# 11-M2_RCB_MUX.net
KiCad netlist of a schematic drawn in Altium Designer
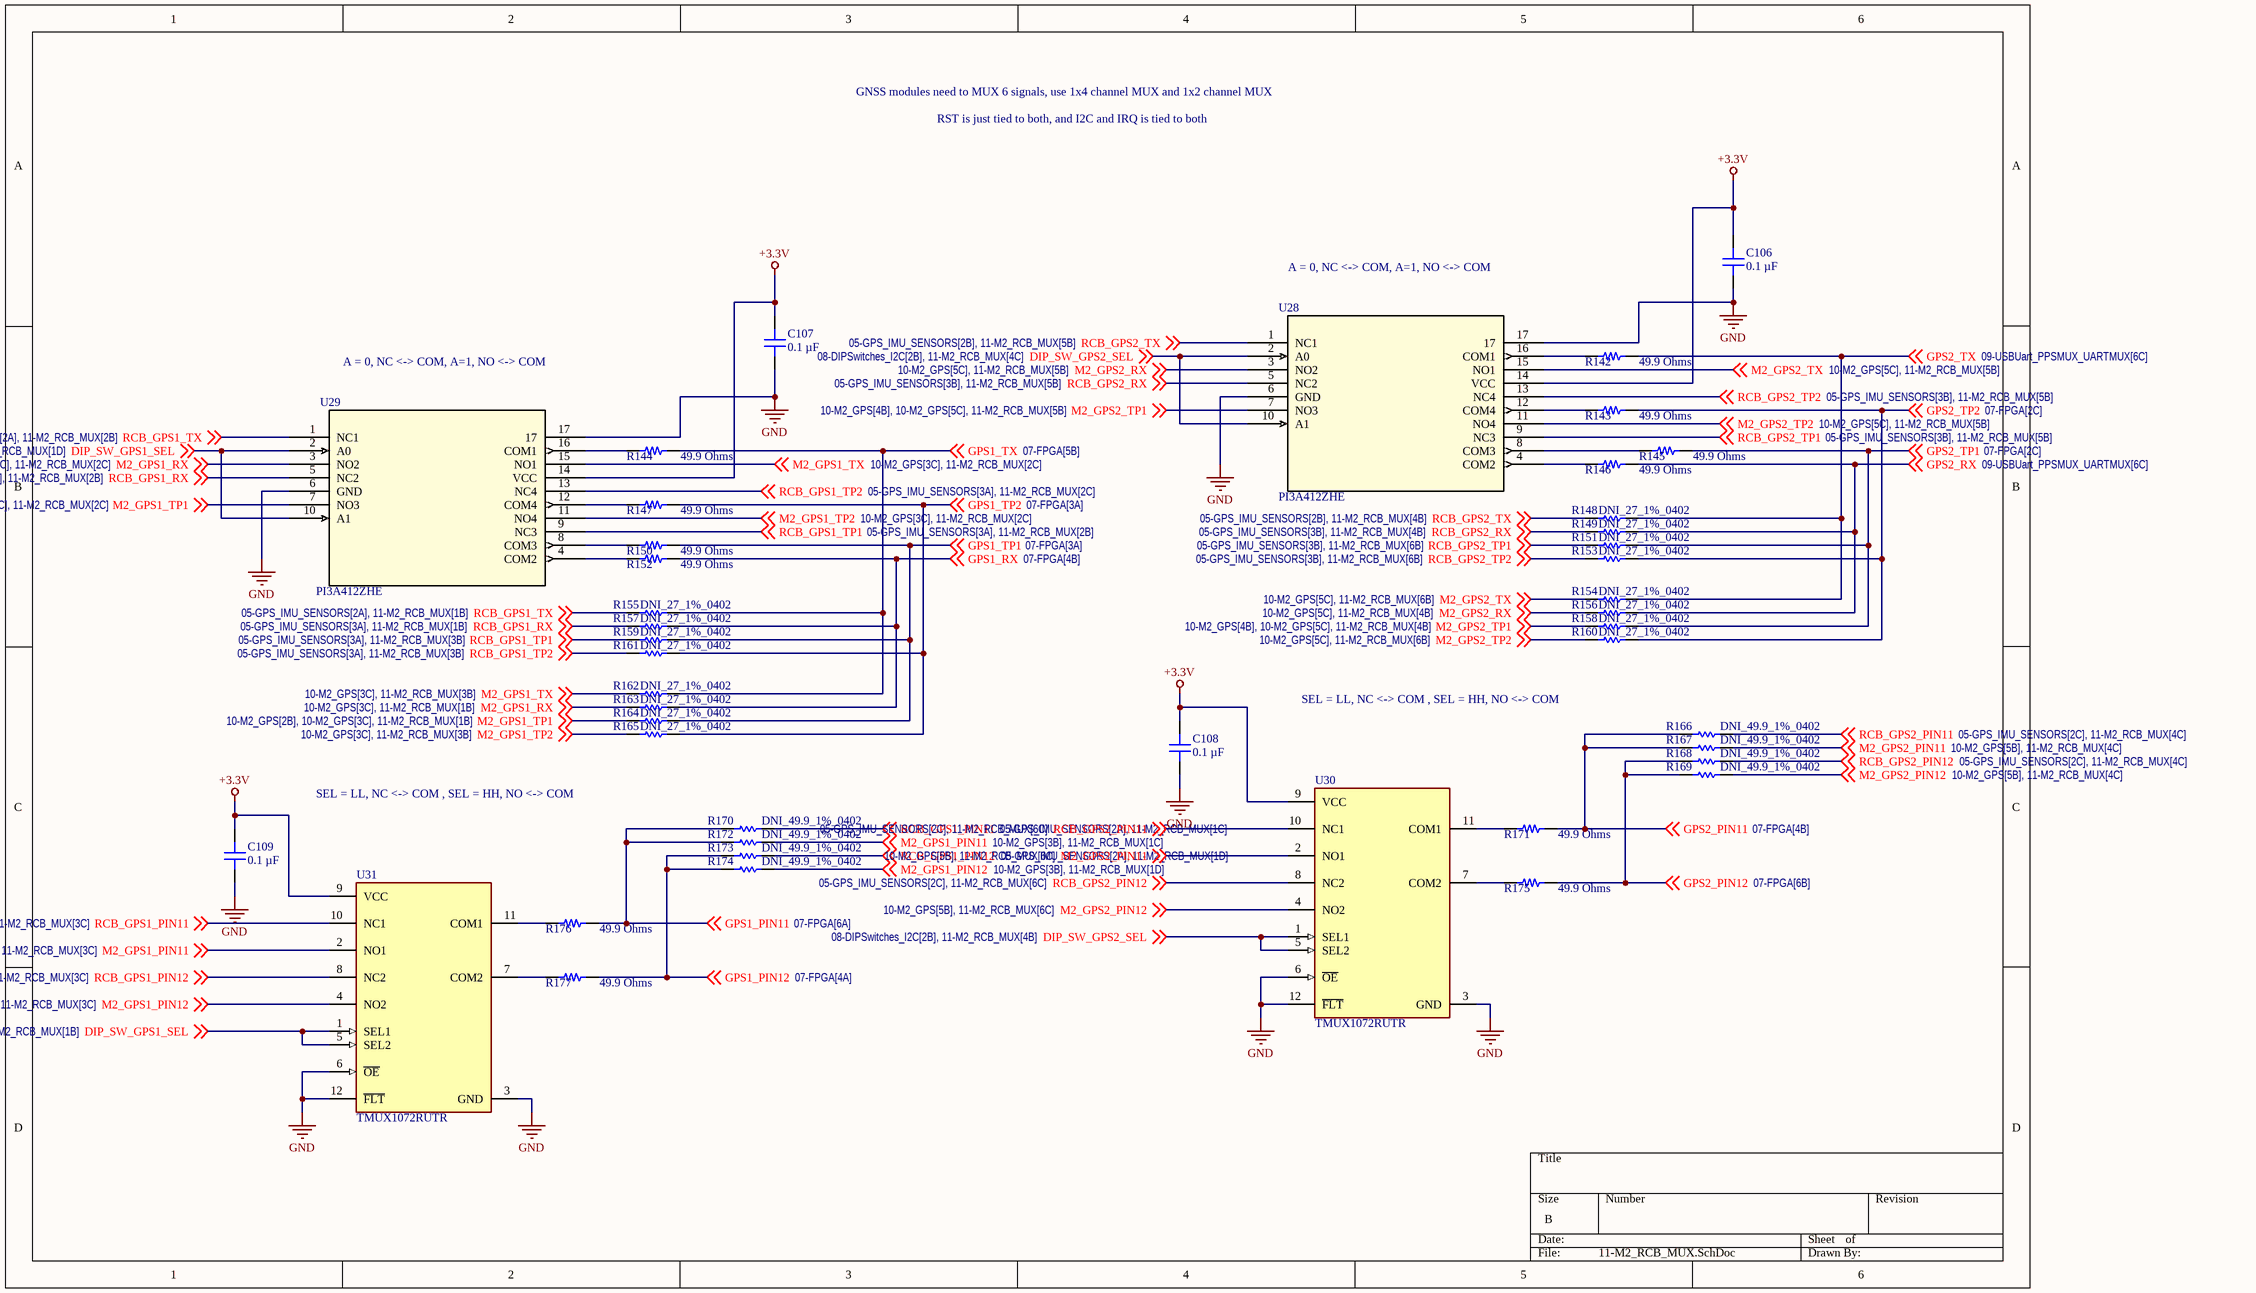
[diagram p0: 11-M2_RCB_MUX.SchDoc]

(export (version "E")
  (design (tool "Eeschema 10.0.6"))
  (components
    (comp (ref "C106")
      (value "0.1 µF")
      (footprint "CAP 0402_1005")
      (description "CAP CER 0.1UF 50V X7R 0402")
      (fields (field (name "TOLERANCE") "±10%") (field (name "PART NUMBER") "CC0402KRX7R9BB104"))
      (libsource (lib "Celestial Altium Library - altium_library") (part "Capacitor"))
    )
    (comp (ref "C107")
      (value "0.1 µF")
      (footprint "CAP 0402_1005")
      (description "CAP CER 0.1UF 50V X7R 0402")
      (fields (field (name "TOLERANCE") "±10%") (field (name "PART NUMBER") "CC0402KRX7R9BB104"))
      (libsource (lib "Celestial Altium Library - altium_library") (part "Capacitor"))
    )
    (comp (ref "C108")
      (value "0.1 µF")
      (footprint "CAP 0402_1005")
      (description "CAP CER 0.1UF 50V X7R 0402")
      (fields (field (name "TOLERANCE") "±10%") (field (name "PART NUMBER") "CC0402KRX7R9BB104"))
      (libsource (lib "Celestial Altium Library - altium_library") (part "Capacitor"))
    )
    (comp (ref "C109")
      (value "0.1 µF")
      (footprint "CAP 0402_1005")
      (description "CAP CER 0.1UF 50V X7R 0402")
      (fields (field (name "TOLERANCE") "±10%") (field (name "PART NUMBER") "CC0402KRX7R9BB104"))
      (libsource (lib "Celestial Altium Library - altium_library") (part "Capacitor"))
    )
    (comp (ref "R142")
      (value "49.9 Ohms")
      (footprint "YAGEO RES 0402_1005")
      (description "RES 49.9 OHM 1% 1/16W 0402")
      (fields (field (name "MANUFACTURER") "Yageo") (field (name "PART NUMBER") "RC0402FR-0749R9L"))
      (libsource (lib "Celestial Altium Library - altium_library") (part "Resistor"))
    )
    (comp (ref "R143")
      (value "49.9 Ohms")
      (footprint "YAGEO RES 0402_1005")
      (description "RES 49.9 OHM 1% 1/16W 0402")
      (fields (field (name "MANUFACTURER") "Yageo") (field (name "PART NUMBER") "RC0402FR-0749R9L"))
      (libsource (lib "Celestial Altium Library - altium_library") (part "Resistor"))
    )
    (comp (ref "R144")
      (value "49.9 Ohms")
      (footprint "YAGEO RES 0402_1005")
      (description "RES 49.9 OHM 1% 1/16W 0402")
      (fields (field (name "MANUFACTURER") "Yageo") (field (name "PART NUMBER") "RC0402FR-0749R9L"))
      (libsource (lib "Celestial Altium Library - altium_library") (part "Resistor"))
    )
    (comp (ref "R145")
      (value "49.9 Ohms")
      (footprint "YAGEO RES 0402_1005")
      (description "RES 49.9 OHM 1% 1/16W 0402")
      (fields (field (name "MANUFACTURER") "Yageo") (field (name "PART NUMBER") "RC0402FR-0749R9L"))
      (libsource (lib "Celestial Altium Library - altium_library") (part "Resistor"))
    )
    (comp (ref "R146")
      (value "49.9 Ohms")
      (footprint "YAGEO RES 0402_1005")
      (description "RES 49.9 OHM 1% 1/16W 0402")
      (fields (field (name "MANUFACTURER") "Yageo") (field (name "PART NUMBER") "RC0402FR-0749R9L"))
      (libsource (lib "Celestial Altium Library - altium_library") (part "Resistor"))
    )
    (comp (ref "R147")
      (value "49.9 Ohms")
      (footprint "YAGEO RES 0402_1005")
      (description "RES 49.9 OHM 1% 1/16W 0402")
      (fields (field (name "MANUFACTURER") "Yageo") (field (name "PART NUMBER") "RC0402FR-0749R9L"))
      (libsource (lib "Celestial Altium Library - altium_library") (part "Resistor"))
    )
    (comp (ref "R148")
      (value "DNI_27_1%_0402")
      (footprint "RESC1005X40X25NL05T05")
      (fields (field (name "PART NUMBER") "CRCW040227R0FKED") (field (name "MANUFACTURER") "Vishay Dale"))
      (libsource (lib "Altium Content Vault") (part "RES"))
    )
    (comp (ref "R149")
      (value "DNI_27_1%_0402")
      (footprint "RESC1005X40X25NL05T05")
      (fields (field (name "PART NUMBER") "CRCW040227R0FKED") (field (name "MANUFACTURER") "Vishay Dale"))
      (libsource (lib "Altium Content Vault") (part "RES"))
    )
    (comp (ref "R150")
      (value "49.9 Ohms")
      (footprint "YAGEO RES 0402_1005")
      (description "RES 49.9 OHM 1% 1/16W 0402")
      (fields (field (name "MANUFACTURER") "Yageo") (field (name "PART NUMBER") "RC0402FR-0749R9L"))
      (libsource (lib "Celestial Altium Library - altium_library") (part "Resistor"))
    )
    (comp (ref "R151")
      (value "DNI_27_1%_0402")
      (footprint "RESC1005X40X25NL05T05")
      (fields (field (name "PART NUMBER") "CRCW040227R0FKED") (field (name "MANUFACTURER") "Vishay Dale"))
      (libsource (lib "Altium Content Vault") (part "RES"))
    )
    (comp (ref "R152")
      (value "49.9 Ohms")
      (footprint "YAGEO RES 0402_1005")
      (description "RES 49.9 OHM 1% 1/16W 0402")
      (fields (field (name "MANUFACTURER") "Yageo") (field (name "PART NUMBER") "RC0402FR-0749R9L"))
      (libsource (lib "Celestial Altium Library - altium_library") (part "Resistor"))
    )
    (comp (ref "R153")
      (value "DNI_27_1%_0402")
      (footprint "RESC1005X40X25NL05T05")
      (fields (field (name "PART NUMBER") "CRCW040227R0FKED") (field (name "MANUFACTURER") "Vishay Dale"))
      (libsource (lib "Altium Content Vault") (part "RES"))
    )
    (comp (ref "R154")
      (value "DNI_27_1%_0402")
      (footprint "RESC1005X40X25NL05T05")
      (fields (field (name "PART NUMBER") "CRCW040227R0FKED") (field (name "MANUFACTURER") "Vishay Dale"))
      (libsource (lib "Altium Content Vault") (part "RES"))
    )
    (comp (ref "R155")
      (value "DNI_27_1%_0402")
      (footprint "RESC1005X40X25NL05T05")
      (fields (field (name "PART NUMBER") "CRCW040227R0FKED") (field (name "MANUFACTURER") "Vishay Dale"))
      (libsource (lib "Altium Content Vault") (part "RES"))
    )
    (comp (ref "R156")
      (value "DNI_27_1%_0402")
      (footprint "RESC1005X40X25NL05T05")
      (fields (field (name "PART NUMBER") "CRCW040227R0FKED") (field (name "MANUFACTURER") "Vishay Dale"))
      (libsource (lib "Altium Content Vault") (part "RES"))
    )
    (comp (ref "R157")
      (value "DNI_27_1%_0402")
      (footprint "RESC1005X40X25NL05T05")
      (fields (field (name "PART NUMBER") "CRCW040227R0FKED") (field (name "MANUFACTURER") "Vishay Dale"))
      (libsource (lib "Altium Content Vault") (part "RES"))
    )
    (comp (ref "R158")
      (value "DNI_27_1%_0402")
      (footprint "RESC1005X40X25NL05T05")
      (fields (field (name "PART NUMBER") "CRCW040227R0FKED") (field (name "MANUFACTURER") "Vishay Dale"))
      (libsource (lib "Altium Content Vault") (part "RES"))
    )
    (comp (ref "R159")
      (value "DNI_27_1%_0402")
      (footprint "RESC1005X40X25NL05T05")
      (fields (field (name "PART NUMBER") "CRCW040227R0FKED") (field (name "MANUFACTURER") "Vishay Dale"))
      (libsource (lib "Altium Content Vault") (part "RES"))
    )
    (comp (ref "R160")
      (value "DNI_27_1%_0402")
      (footprint "RESC1005X40X25NL05T05")
      (fields (field (name "PART NUMBER") "CRCW040227R0FKED") (field (name "MANUFACTURER") "Vishay Dale"))
      (libsource (lib "Altium Content Vault") (part "RES"))
    )
    (comp (ref "R161")
      (value "DNI_27_1%_0402")
      (footprint "RESC1005X40X25NL05T05")
      (fields (field (name "PART NUMBER") "CRCW040227R0FKED") (field (name "MANUFACTURER") "Vishay Dale"))
      (libsource (lib "Altium Content Vault") (part "RES"))
    )
    (comp (ref "R162")
      (value "DNI_27_1%_0402")
      (footprint "RESC1005X40X25NL05T05")
      (fields (field (name "PART NUMBER") "CRCW040227R0FKED") (field (name "MANUFACTURER") "Vishay Dale"))
      (libsource (lib "Altium Content Vault") (part "RES"))
    )
    (comp (ref "R163")
      (value "DNI_27_1%_0402")
      (footprint "RESC1005X40X25NL05T05")
      (fields (field (name "PART NUMBER") "CRCW040227R0FKED") (field (name "MANUFACTURER") "Vishay Dale"))
      (libsource (lib "Altium Content Vault") (part "RES"))
    )
    (comp (ref "R164")
      (value "DNI_27_1%_0402")
      (footprint "RESC1005X40X25NL05T05")
      (fields (field (name "PART NUMBER") "CRCW040227R0FKED") (field (name "MANUFACTURER") "Vishay Dale"))
      (libsource (lib "Altium Content Vault") (part "RES"))
    )
    (comp (ref "R165")
      (value "DNI_27_1%_0402")
      (footprint "RESC1005X40X25NL05T05")
      (fields (field (name "PART NUMBER") "CRCW040227R0FKED") (field (name "MANUFACTURER") "Vishay Dale"))
      (libsource (lib "Altium Content Vault") (part "RES"))
    )
    (comp (ref "R166")
      (value "DNI_49.9_1%_0402")
      (footprint "RESC1005X40X25LL05T10")
      (fields (field (name "MANUFACTURER") "Yageo / Phycomp") (field (name "PART NUMBER") "RC0402FR-0749R9L"))
      (libsource (lib "Altium Content Vault") (part "RES"))
    )
    (comp (ref "R167")
      (value "DNI_49.9_1%_0402")
      (footprint "RESC1005X40X25LL05T10")
      (fields (field (name "MANUFACTURER") "Yageo / Phycomp") (field (name "PART NUMBER") "RC0402FR-0749R9L"))
      (libsource (lib "Altium Content Vault") (part "RES"))
    )
    (comp (ref "R168")
      (value "DNI_49.9_1%_0402")
      (footprint "RESC1005X40X25LL05T10")
      (fields (field (name "MANUFACTURER") "Yageo / Phycomp") (field (name "PART NUMBER") "RC0402FR-0749R9L"))
      (libsource (lib "Altium Content Vault") (part "RES"))
    )
    (comp (ref "R169")
      (value "DNI_49.9_1%_0402")
      (footprint "RESC1005X40X25LL05T10")
      (fields (field (name "MANUFACTURER") "Yageo / Phycomp") (field (name "PART NUMBER") "RC0402FR-0749R9L"))
      (libsource (lib "Altium Content Vault") (part "RES"))
    )
    (comp (ref "R170")
      (value "DNI_49.9_1%_0402")
      (footprint "RESC1005X40X25LL05T10")
      (fields (field (name "MANUFACTURER") "Yageo / Phycomp") (field (name "PART NUMBER") "RC0402FR-0749R9L"))
      (libsource (lib "Altium Content Vault") (part "RES"))
    )
    (comp (ref "R171")
      (value "49.9 Ohms")
      (footprint "YAGEO RES 0402_1005")
      (description "RES 49.9 OHM 1% 1/16W 0402")
      (fields (field (name "MANUFACTURER") "Yageo") (field (name "PART NUMBER") "RC0402FR-0749R9L"))
      (libsource (lib "Celestial Altium Library - altium_library") (part "Resistor"))
    )
    (comp (ref "R172")
      (value "DNI_49.9_1%_0402")
      (footprint "RESC1005X40X25LL05T10")
      (fields (field (name "MANUFACTURER") "Yageo / Phycomp") (field (name "PART NUMBER") "RC0402FR-0749R9L"))
      (libsource (lib "Altium Content Vault") (part "RES"))
    )
    (comp (ref "R173")
      (value "DNI_49.9_1%_0402")
      (footprint "RESC1005X40X25LL05T10")
      (fields (field (name "MANUFACTURER") "Yageo / Phycomp") (field (name "PART NUMBER") "RC0402FR-0749R9L"))
      (libsource (lib "Altium Content Vault") (part "RES"))
    )
    (comp (ref "R174")
      (value "DNI_49.9_1%_0402")
      (footprint "RESC1005X40X25LL05T10")
      (fields (field (name "MANUFACTURER") "Yageo / Phycomp") (field (name "PART NUMBER") "RC0402FR-0749R9L"))
      (libsource (lib "Altium Content Vault") (part "RES"))
    )
    (comp (ref "R175")
      (value "49.9 Ohms")
      (footprint "YAGEO RES 0402_1005")
      (description "RES 49.9 OHM 1% 1/16W 0402")
      (fields (field (name "MANUFACTURER") "Yageo") (field (name "PART NUMBER") "RC0402FR-0749R9L"))
      (libsource (lib "Celestial Altium Library - altium_library") (part "Resistor"))
    )
    (comp (ref "R176")
      (value "49.9 Ohms")
      (footprint "YAGEO RES 0402_1005")
      (description "RES 49.9 OHM 1% 1/16W 0402")
      (fields (field (name "MANUFACTURER") "Yageo") (field (name "PART NUMBER") "RC0402FR-0749R9L"))
      (libsource (lib "Celestial Altium Library - altium_library") (part "Resistor"))
    )
    (comp (ref "R177")
      (value "49.9 Ohms")
      (footprint "YAGEO RES 0402_1005")
      (description "RES 49.9 OHM 1% 1/16W 0402")
      (fields (field (name "MANUFACTURER") "Yageo") (field (name "PART NUMBER") "RC0402FR-0749R9L"))
      (libsource (lib "Celestial Altium Library - altium_library") (part "Resistor"))
    )
    (comp (ref "U28")
      (value "PI3A412ZHE")
      (footprint "ZH16_PER")
      (description "No Description Available")
      (libsource (lib "PI3A412ZHE") (part "PI3A412ZHE"))
    )
    (comp (ref "U29")
      (value "PI3A412ZHE")
      (footprint "ZH16_PER")
      (description "No Description Available")
      (libsource (lib "PI3A412ZHE") (part "PI3A412ZHE"))
    )
    (comp (ref "U30")
      (value "TMUX1072RUTR")
      (footprint "FP-RUT0012A-MFG")
      (description "IC SWITCH SPDT DUAL 12UQFN")
      (libsource (lib "Altium Content Vault") (part "12a319ab100cd6cfe745e35972674f5"))
    )
    (comp (ref "U31")
      (value "TMUX1072RUTR")
      (footprint "FP-RUT0012A-MFG")
      (description "IC SWITCH SPDT DUAL 12UQFN")
      (libsource (lib "Altium Content Vault") (part "12a319ab100cd6cfe745e35972674f5"))
    )
  )
  (nets
    (net (code "1") (name "+3.3V") (class "Default")
      (node (ref "C106") (pin "2") (pinfunction "2_2") (pintype "passive"))
      (node (ref "C107") (pin "2") (pinfunction "2_2") (pintype "passive"))
      (node (ref "C108") (pin "1") (pinfunction "1_1") (pintype "passive"))
      (node (ref "C109") (pin "1") (pinfunction "1_1") (pintype "passive"))
      (node (ref "U28") (pin "14") (pinfunction "VCC_14") (pintype "power_in"))
      (node (ref "U29") (pin "14") (pinfunction "VCC_14") (pintype "power_in"))
      (node (ref "U30") (pin "9") (pinfunction "VCC_9") (pintype "power_in"))
      (node (ref "U31") (pin "9") (pinfunction "VCC_9") (pintype "power_in"))
    )
    (net (code "2") (name "DIP_SW_GPS1_SEL") (class "Default")
      (node (ref "U29") (pin "10") (pinfunction "A1_10") (pintype "input"))
      (node (ref "U29") (pin "2") (pinfunction "A0_2") (pintype "input"))
      (node (ref "U31") (pin "1") (pinfunction "SEL1_1") (pintype "input"))
      (node (ref "U31") (pin "5") (pinfunction "SEL2_5") (pintype "input"))
    )
    (net (code "3") (name "DIP_SW_GPS2_SEL") (class "Default")
      (node (ref "U28") (pin "10") (pinfunction "A1_10") (pintype "input"))
      (node (ref "U28") (pin "2") (pinfunction "A0_2") (pintype "input"))
      (node (ref "U30") (pin "1") (pinfunction "SEL1_1") (pintype "input"))
      (node (ref "U30") (pin "5") (pinfunction "SEL2_5") (pintype "input"))
    )
    (net (code "4") (name "GND") (class "Default")
      (node (ref "C106") (pin "1") (pinfunction "1_1") (pintype "passive"))
      (node (ref "C107") (pin "1") (pinfunction "1_1") (pintype "passive"))
      (node (ref "C108") (pin "2") (pinfunction "2_2") (pintype "passive"))
      (node (ref "C109") (pin "2") (pinfunction "2_2") (pintype "passive"))
      (node (ref "U28") (pin "17") (pinfunction "17_17") (pintype "passive"))
      (node (ref "U28") (pin "6") (pinfunction "GND_6") (pintype "power_in"))
      (node (ref "U29") (pin "17") (pinfunction "17_17") (pintype "passive"))
      (node (ref "U29") (pin "6") (pinfunction "GND_6") (pintype "power_in"))
      (node (ref "U30") (pin "12") (pinfunction "~{FLT}_12") (pintype "open_collector"))
      (node (ref "U30") (pin "3") (pinfunction "GND_3") (pintype "power_in"))
      (node (ref "U30") (pin "6") (pinfunction "~{OE}_6") (pintype "input"))
      (node (ref "U31") (pin "12") (pinfunction "~{FLT}_12") (pintype "open_collector"))
      (node (ref "U31") (pin "3") (pinfunction "GND_3") (pintype "power_in"))
      (node (ref "U31") (pin "6") (pinfunction "~{OE}_6") (pintype "input"))
    )
    (net (code "5") (name "GPS1_PIN11") (class "Default")
      (node (ref "R170") (pin "1") (pinfunction "1_1") (pintype "passive"))
      (node (ref "R172") (pin "1") (pinfunction "1_1") (pintype "passive"))
      (node (ref "R176") (pin "2") (pinfunction "2_2") (pintype "passive"))
    )
    (net (code "6") (name "GPS1_PIN12") (class "Default")
      (node (ref "R173") (pin "1") (pinfunction "1_1") (pintype "passive"))
      (node (ref "R174") (pin "1") (pinfunction "1_1") (pintype "passive"))
      (node (ref "R177") (pin "2") (pinfunction "2_2") (pintype "passive"))
    )
    (net (code "7") (name "GPS1_RX") (class "Default")
      (node (ref "R152") (pin "2") (pinfunction "2_2") (pintype "passive"))
      (node (ref "R157") (pin "2") (pinfunction "2_2") (pintype "passive"))
      (node (ref "R163") (pin "2") (pinfunction "2_2") (pintype "passive"))
    )
    (net (code "8") (name "GPS1_TP1") (class "Default")
      (node (ref "R150") (pin "2") (pinfunction "2_2") (pintype "passive"))
      (node (ref "R159") (pin "2") (pinfunction "2_2") (pintype "passive"))
      (node (ref "R164") (pin "2") (pinfunction "2_2") (pintype "passive"))
    )
    (net (code "9") (name "GPS1_TP2") (class "Default")
      (node (ref "R147") (pin "2") (pinfunction "2_2") (pintype "passive"))
      (node (ref "R161") (pin "2") (pinfunction "2_2") (pintype "passive"))
      (node (ref "R165") (pin "2") (pinfunction "2_2") (pintype "passive"))
    )
    (net (code "10") (name "GPS1_TX") (class "Default")
      (node (ref "R144") (pin "2") (pinfunction "2_2") (pintype "passive"))
      (node (ref "R155") (pin "2") (pinfunction "2_2") (pintype "passive"))
      (node (ref "R162") (pin "2") (pinfunction "2_2") (pintype "passive"))
    )
    (net (code "11") (name "GPS2_PIN11") (class "Default")
      (node (ref "R166") (pin "1") (pinfunction "1_1") (pintype "passive"))
      (node (ref "R167") (pin "1") (pinfunction "1_1") (pintype "passive"))
      (node (ref "R171") (pin "2") (pinfunction "2_2") (pintype "passive"))
    )
    (net (code "12") (name "GPS2_PIN12") (class "Default")
      (node (ref "R168") (pin "1") (pinfunction "1_1") (pintype "passive"))
      (node (ref "R169") (pin "1") (pinfunction "1_1") (pintype "passive"))
      (node (ref "R175") (pin "2") (pinfunction "2_2") (pintype "passive"))
    )
    (net (code "13") (name "GPS2_RX") (class "Default")
      (node (ref "R146") (pin "2") (pinfunction "2_2") (pintype "passive"))
      (node (ref "R149") (pin "2") (pinfunction "2_2") (pintype "passive"))
      (node (ref "R156") (pin "2") (pinfunction "2_2") (pintype "passive"))
    )
    (net (code "14") (name "GPS2_TP1") (class "Default")
      (node (ref "R145") (pin "2") (pinfunction "2_2") (pintype "passive"))
      (node (ref "R151") (pin "2") (pinfunction "2_2") (pintype "passive"))
      (node (ref "R158") (pin "2") (pinfunction "2_2") (pintype "passive"))
    )
    (net (code "15") (name "GPS2_TP2") (class "Default")
      (node (ref "R143") (pin "2") (pinfunction "2_2") (pintype "passive"))
      (node (ref "R153") (pin "2") (pinfunction "2_2") (pintype "passive"))
      (node (ref "R160") (pin "2") (pinfunction "2_2") (pintype "passive"))
    )
    (net (code "16") (name "GPS2_TX") (class "Default")
      (node (ref "R142") (pin "2") (pinfunction "2_2") (pintype "passive"))
      (node (ref "R148") (pin "2") (pinfunction "2_2") (pintype "passive"))
      (node (ref "R154") (pin "2") (pinfunction "2_2") (pintype "passive"))
    )
    (net (code "17") (name "M2_GPS1_PIN11") (class "Default")
      (node (ref "R172") (pin "2") (pinfunction "2_2") (pintype "passive"))
      (node (ref "U31") (pin "2") (pinfunction "NO1_2") (pintype "passive"))
    )
    (net (code "18") (name "M2_GPS1_PIN12") (class "Default")
      (node (ref "R174") (pin "2") (pinfunction "2_2") (pintype "passive"))
      (node (ref "U31") (pin "4") (pinfunction "NO2_4") (pintype "passive"))
    )
    (net (code "19") (name "M2_GPS1_RX") (class "Default")
      (node (ref "R163") (pin "1") (pinfunction "1_1") (pintype "passive"))
      (node (ref "U29") (pin "3") (pinfunction "NO2_3") (pintype "passive"))
    )
    (net (code "20") (name "M2_GPS1_TP1") (class "Default")
      (node (ref "R164") (pin "1") (pinfunction "1_1") (pintype "passive"))
      (node (ref "U29") (pin "7") (pinfunction "NO3_7") (pintype "passive"))
    )
    (net (code "21") (name "M2_GPS1_TP2") (class "Default")
      (node (ref "R165") (pin "1") (pinfunction "1_1") (pintype "passive"))
      (node (ref "U29") (pin "11") (pinfunction "NO4_11") (pintype "passive"))
    )
    (net (code "22") (name "M2_GPS1_TX") (class "Default")
      (node (ref "R162") (pin "1") (pinfunction "1_1") (pintype "passive"))
      (node (ref "U29") (pin "15") (pinfunction "NO1_15") (pintype "passive"))
    )
    (net (code "23") (name "M2_GPS2_PIN11") (class "Default")
      (node (ref "R167") (pin "2") (pinfunction "2_2") (pintype "passive"))
      (node (ref "U30") (pin "2") (pinfunction "NO1_2") (pintype "passive"))
    )
    (net (code "24") (name "M2_GPS2_PIN12") (class "Default")
      (node (ref "R169") (pin "2") (pinfunction "2_2") (pintype "passive"))
      (node (ref "U30") (pin "4") (pinfunction "NO2_4") (pintype "passive"))
    )
    (net (code "25") (name "M2_GPS2_RX") (class "Default")
      (node (ref "R156") (pin "1") (pinfunction "1_1") (pintype "passive"))
      (node (ref "U28") (pin "3") (pinfunction "NO2_3") (pintype "passive"))
    )
    (net (code "26") (name "M2_GPS2_TP1") (class "Default")
      (node (ref "R158") (pin "1") (pinfunction "1_1") (pintype "passive"))
      (node (ref "U28") (pin "7") (pinfunction "NO3_7") (pintype "passive"))
    )
    (net (code "27") (name "M2_GPS2_TP2") (class "Default")
      (node (ref "R160") (pin "1") (pinfunction "1_1") (pintype "passive"))
      (node (ref "U28") (pin "11") (pinfunction "NO4_11") (pintype "passive"))
    )
    (net (code "28") (name "M2_GPS2_TX") (class "Default")
      (node (ref "R154") (pin "1") (pinfunction "1_1") (pintype "passive"))
      (node (ref "U28") (pin "15") (pinfunction "NO1_15") (pintype "passive"))
    )
    (net (code "29") (name "Net-(U28-COM1)") (class "Default")
      (node (ref "R142") (pin "1") (pinfunction "1_1") (pintype "passive"))
      (node (ref "U28") (pin "16") (pinfunction "COM1_16") (pintype "output"))
    )
    (net (code "30") (name "Net-(U28-COM2)") (class "Default")
      (node (ref "R146") (pin "1") (pinfunction "1_1") (pintype "passive"))
      (node (ref "U28") (pin "4") (pinfunction "COM2_4") (pintype "output"))
    )
    (net (code "31") (name "Net-(U28-COM3)") (class "Default")
      (node (ref "R145") (pin "1") (pinfunction "1_1") (pintype "passive"))
      (node (ref "U28") (pin "8") (pinfunction "COM3_8") (pintype "output"))
    )
    (net (code "32") (name "Net-(U28-COM4)") (class "Default")
      (node (ref "R143") (pin "1") (pinfunction "1_1") (pintype "passive"))
      (node (ref "U28") (pin "12") (pinfunction "COM4_12") (pintype "output"))
    )
    (net (code "33") (name "Net-(U29-COM1)") (class "Default")
      (node (ref "R144") (pin "1") (pinfunction "1_1") (pintype "passive"))
      (node (ref "U29") (pin "16") (pinfunction "COM1_16") (pintype "output"))
    )
    (net (code "34") (name "Net-(U29-COM2)") (class "Default")
      (node (ref "R152") (pin "1") (pinfunction "1_1") (pintype "passive"))
      (node (ref "U29") (pin "4") (pinfunction "COM2_4") (pintype "output"))
    )
    (net (code "35") (name "Net-(U29-COM3)") (class "Default")
      (node (ref "R150") (pin "1") (pinfunction "1_1") (pintype "passive"))
      (node (ref "U29") (pin "8") (pinfunction "COM3_8") (pintype "output"))
    )
    (net (code "36") (name "Net-(U29-COM4)") (class "Default")
      (node (ref "R147") (pin "1") (pinfunction "1_1") (pintype "passive"))
      (node (ref "U29") (pin "12") (pinfunction "COM4_12") (pintype "output"))
    )
    (net (code "37") (name "Net-(U30-COM1)") (class "Default")
      (node (ref "R171") (pin "1") (pinfunction "1_1") (pintype "passive"))
      (node (ref "U30") (pin "11") (pinfunction "COM1_11") (pintype "passive"))
    )
    (net (code "38") (name "Net-(U30-COM2)") (class "Default")
      (node (ref "R175") (pin "1") (pinfunction "1_1") (pintype "passive"))
      (node (ref "U30") (pin "7") (pinfunction "COM2_7") (pintype "passive"))
    )
    (net (code "39") (name "Net-(U31-COM1)") (class "Default")
      (node (ref "R176") (pin "1") (pinfunction "1_1") (pintype "passive"))
      (node (ref "U31") (pin "11") (pinfunction "COM1_11") (pintype "passive"))
    )
    (net (code "40") (name "Net-(U31-COM2)") (class "Default")
      (node (ref "R177") (pin "1") (pinfunction "1_1") (pintype "passive"))
      (node (ref "U31") (pin "7") (pinfunction "COM2_7") (pintype "passive"))
    )
    (net (code "41") (name "RCB_GPS1_PIN11") (class "Default")
      (node (ref "R170") (pin "2") (pinfunction "2_2") (pintype "passive"))
      (node (ref "U31") (pin "10") (pinfunction "NC1_10") (pintype "passive"))
    )
    (net (code "42") (name "RCB_GPS1_PIN12") (class "Default")
      (node (ref "R173") (pin "2") (pinfunction "2_2") (pintype "passive"))
      (node (ref "U31") (pin "8") (pinfunction "NC2_8") (pintype "passive"))
    )
    (net (code "43") (name "RCB_GPS1_RX") (class "Default")
      (node (ref "R157") (pin "1") (pinfunction "1_1") (pintype "passive"))
      (node (ref "U29") (pin "5") (pinfunction "NC2_5") (pintype "passive"))
    )
    (net (code "44") (name "RCB_GPS1_TP1") (class "Default")
      (node (ref "R159") (pin "1") (pinfunction "1_1") (pintype "passive"))
      (node (ref "U29") (pin "9") (pinfunction "NC3_9") (pintype "passive"))
    )
    (net (code "45") (name "RCB_GPS1_TP2") (class "Default")
      (node (ref "R161") (pin "1") (pinfunction "1_1") (pintype "passive"))
      (node (ref "U29") (pin "13") (pinfunction "NC4_13") (pintype "passive"))
    )
    (net (code "46") (name "RCB_GPS1_TX") (class "Default")
      (node (ref "R155") (pin "1") (pinfunction "1_1") (pintype "passive"))
      (node (ref "U29") (pin "1") (pinfunction "NC1_1") (pintype "passive"))
    )
    (net (code "47") (name "RCB_GPS2_PIN11") (class "Default")
      (node (ref "R166") (pin "2") (pinfunction "2_2") (pintype "passive"))
      (node (ref "U30") (pin "10") (pinfunction "NC1_10") (pintype "passive"))
    )
    (net (code "48") (name "RCB_GPS2_PIN12") (class "Default")
      (node (ref "R168") (pin "2") (pinfunction "2_2") (pintype "passive"))
      (node (ref "U30") (pin "8") (pinfunction "NC2_8") (pintype "passive"))
    )
    (net (code "49") (name "RCB_GPS2_RX") (class "Default")
      (node (ref "R149") (pin "1") (pinfunction "1_1") (pintype "passive"))
      (node (ref "U28") (pin "5") (pinfunction "NC2_5") (pintype "passive"))
    )
    (net (code "50") (name "RCB_GPS2_TP1") (class "Default")
      (node (ref "R151") (pin "1") (pinfunction "1_1") (pintype "passive"))
      (node (ref "U28") (pin "9") (pinfunction "NC3_9") (pintype "passive"))
    )
    (net (code "51") (name "RCB_GPS2_TP2") (class "Default")
      (node (ref "R153") (pin "1") (pinfunction "1_1") (pintype "passive"))
      (node (ref "U28") (pin "13") (pinfunction "NC4_13") (pintype "passive"))
    )
    (net (code "52") (name "RCB_GPS2_TX") (class "Default")
      (node (ref "R148") (pin "1") (pinfunction "1_1") (pintype "passive"))
      (node (ref "U28") (pin "1") (pinfunction "NC1_1") (pintype "passive"))
    )
  )
)
